# TheremineB.net
KiCad netlist of a schematic drawn in Altium Designer
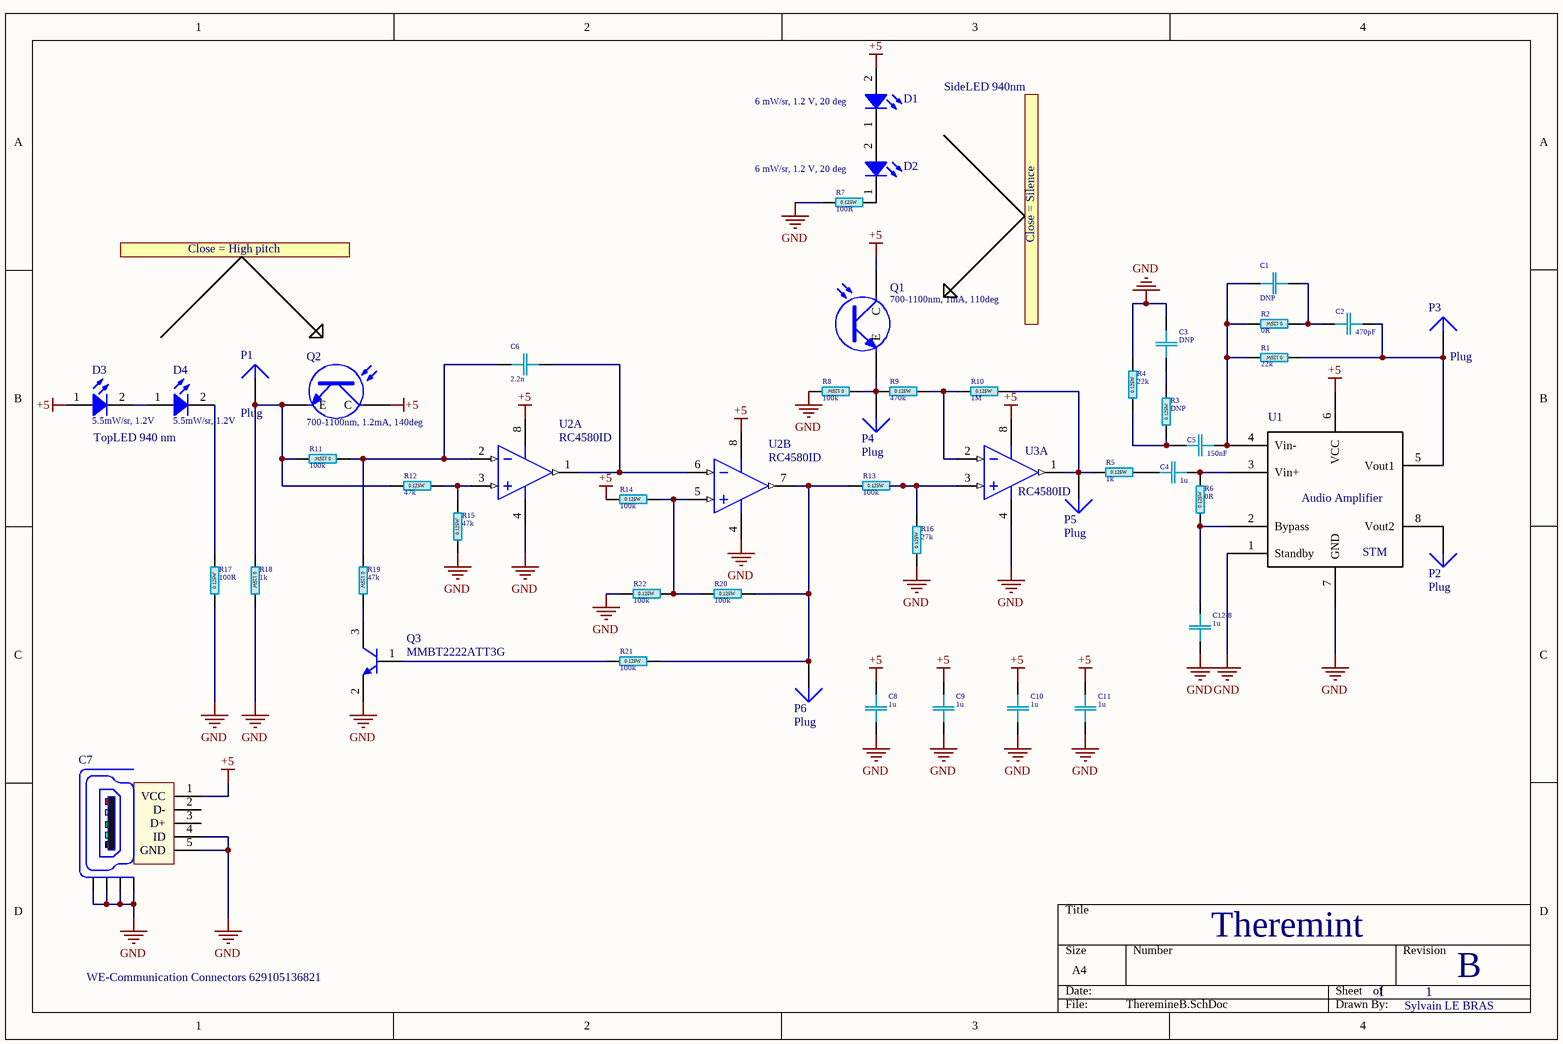
[diagram p0: TheremineB.SchDoc]

(export (version "E")
  (design (tool "Eeschema 10.0.6"))
  (components
    (comp (ref "C1")
      (value "DNP")
      (footprint "C 0805(2012)x1.25")
      (description "SMD 0805     16V X7R 10%")
      (fields
        (field (name "PART NUMBER") "CL21B105KBFNNNF")
        (field (name "MANUFACTURER") "Samsung")
        (field (name "PUBLISHER") "Hefest")
      )
      (libsource (lib "SMD Passive") (part "C 0805    16V X7R - 1u"))
    )
    (comp (ref "C2")
      (value "470pF")
      (footprint "C 0805(2012)x1.25")
      (description "SMD 0805     16V X7R 10%")
      (fields
        (field (name "PART NUMBER") "CL21B105KBFNNNF")
        (field (name "MANUFACTURER") "Samsung")
        (field (name "PUBLISHER") "Hefest")
      )
      (libsource (lib "SMD Passive") (part "C 0805    16V X7R - 1u"))
    )
    (comp (ref "C3")
      (value "DNP")
      (footprint "C 0805(2012)x1.25")
      (description "SMD 0805     16V X7R 10%")
      (fields
        (field (name "PART NUMBER") "CL21B105KBFNNNF")
        (field (name "MANUFACTURER") "Samsung")
        (field (name "PUBLISHER") "Hefest")
      )
      (libsource (lib "SMD Passive") (part "C 0805    16V X7R - 1u"))
    )
    (comp (ref "C4")
      (value "1u")
      (footprint "C 0805(2012)x1.25")
      (description "SMD 0805     16V X7R 10%")
      (fields
        (field (name "PART NUMBER") "CL21B105KBFNNNF")
        (field (name "MANUFACTURER") "Samsung")
        (field (name "PUBLISHER") "Hefest")
      )
      (libsource (lib "SMD Passive") (part "C 0805    16V X7R - 1u"))
    )
    (comp (ref "C5")
      (value "150nF")
      (footprint "C 0805(2012)x1.25")
      (description "SMD 0805     16V X7R 10%")
      (fields
        (field (name "PART NUMBER") "CL21B105KBFNNNF")
        (field (name "MANUFACTURER") "Samsung")
        (field (name "PUBLISHER") "Hefest")
      )
      (libsource (lib "SMD Passive") (part "C 0805    16V X7R - 1u"))
    )
    (comp (ref "C6")
      (value "2.2n")
      (footprint "C 0805(2012)x0.65")
      (description "SMD 0805     50V X7R 10%")
      (fields
        (field (name "PART NUMBER") "CL21B222KBNC")
        (field (name "MANUFACTURER") "Samsung")
        (field (name "PUBLISHER") "Hefest")
      )
      (libsource (lib "SMD Passive") (part "C 0805    50V X7R - 2.2n"))
    )
    (comp (ref "C7")
      (value "WE-Communication Connectors 629105136821")
      (footprint "629105136821")
      (description "WR-COM Micro USB SMT Type B")
      (fields
        (field (name "MANUFACTURER") "Würth Elektronik eiSos GmbH")
        (field (name "PARTNO") "629105136821")
        (field (name "CREATED BY") "Karrer Zheng")
      )
      (libsource (lib "WR-COM USB 2.0 Type B SMT Horizontal") (part "WE-Communication Connectors 629105136821"))
    )
    (comp (ref "C8")
      (value "1u")
      (footprint "C 0805(2012)x1.25")
      (description "SMD 0805     16V X7R 10%")
      (fields
        (field (name "PART NUMBER") "CL21B105KBFNNNF")
        (field (name "MANUFACTURER") "Samsung")
        (field (name "PUBLISHER") "Hefest")
      )
      (libsource (lib "SMD Passive") (part "C 0805    16V X7R - 1u"))
    )
    (comp (ref "C9")
      (value "1u")
      (footprint "C 0805(2012)x1.25")
      (description "SMD 0805     16V X7R 10%")
      (fields
        (field (name "PART NUMBER") "CL21B105KBFNNNF")
        (field (name "MANUFACTURER") "Samsung")
        (field (name "PUBLISHER") "Hefest")
      )
      (libsource (lib "SMD Passive") (part "C 0805    16V X7R - 1u"))
    )
    (comp (ref "C10")
      (value "1u")
      (footprint "C 0805(2012)x1.25")
      (description "SMD 0805     16V X7R 10%")
      (fields
        (field (name "PART NUMBER") "CL21B105KBFNNNF")
        (field (name "MANUFACTURER") "Samsung")
        (field (name "PUBLISHER") "Hefest")
      )
      (libsource (lib "SMD Passive") (part "C 0805    16V X7R - 1u"))
    )
    (comp (ref "C11")
      (value "1u")
      (footprint "C 0805(2012)x1.25")
      (description "SMD 0805     16V X7R 10%")
      (fields
        (field (name "PART NUMBER") "CL21B105KBFNNNF")
        (field (name "MANUFACTURER") "Samsung")
        (field (name "PUBLISHER") "Hefest")
      )
      (libsource (lib "SMD Passive") (part "C 0805    16V X7R - 1u"))
    )
    (comp (ref "C12-8")
      (value "1u")
      (footprint "C 0805(2012)x1.25")
      (description "SMD 0805     16V X7R 10%")
      (fields
        (field (name "PART NUMBER") "CL21B105KBFNNNF")
        (field (name "MANUFACTURER") "Samsung")
        (field (name "PUBLISHER") "Hefest")
      )
      (libsource (lib "SMD Passive") (part "C 0805    16V X7R - 1u"))
    )
    (comp (ref "D1")
      (value "6 mW/sr, 1.2 V, 20 deg")
      (footprint "WL-SISW_1206")
      (description "SMT Infrared Sideview LED Waterclear WL-SISW, size 1206, 6 mW/sr, 1.2 V, 20 deg")
      (fields (field (name "PART NUMBER") "15412094A2070") (field (name "PUBLISHER") "Wurth Elektronik"))
      (libsource (lib "WL-SISW SMT Infrared Sideview LED Waterclear") (part "15412094A2070"))
    )
    (comp (ref "D2")
      (value "6 mW/sr, 1.2 V, 20 deg")
      (footprint "WL-SISW_1206")
      (description "SMT Infrared Sideview LED Waterclear WL-SISW, size 1206, 6 mW/sr, 1.2 V, 20 deg")
      (fields (field (name "PART NUMBER") "15412094A2070") (field (name "PUBLISHER") "Wurth Elektronik"))
      (libsource (lib "WL-SISW SMT Infrared Sideview LED Waterclear") (part "15412094A2070"))
    )
    (comp (ref "D3")
      (value "5.5mW/sr, 1.2V")
      (footprint "WL-SICW_1206_H=1.21mm")
      (description "WL-SICW SMT Chip LED Infrared Waterclear, size 1206, 5.5mW/sr, 1.2V, 90deg")
      (fields (field (name "PART NUMBER") "15412094A9000") (field (name "PUBLISHER") "Wurth Elektronik"))
      (libsource (lib "WL-SICW SMT Chip LED Infrared Waterclear") (part "15412094A9000"))
    )
    (comp (ref "D4")
      (value "5.5mW/sr, 1.2V")
      (footprint "WL-SICW_1206_H=1.21mm")
      (description "WL-SICW SMT Chip LED Infrared Waterclear, size 1206, 5.5mW/sr, 1.2V, 90deg")
      (fields (field (name "PART NUMBER") "15412094A9000") (field (name "PUBLISHER") "Wurth Elektronik"))
      (libsource (lib "WL-SICW SMT Chip LED Infrared Waterclear") (part "15412094A9000"))
    )
    (comp (ref "P1")
      (value "Plug")
      (footprint "PIN1")
      (fields (field (name "PUBLISHER") "Altium Limited"))
      (libsource (lib "Miscellaneous Connectors") (part "Plug"))
    )
    (comp (ref "P2")
      (value "Plug")
      (footprint "PIN1")
      (fields (field (name "PUBLISHER") "Altium Limited"))
      (libsource (lib "Miscellaneous Connectors") (part "Plug"))
    )
    (comp (ref "P3")
      (value "Plug")
      (footprint "PIN1")
      (fields (field (name "PUBLISHER") "Altium Limited"))
      (libsource (lib "Miscellaneous Connectors") (part "Plug"))
    )
    (comp (ref "P4")
      (value "Plug")
      (footprint "PIN1")
      (fields (field (name "PUBLISHER") "Altium Limited"))
      (libsource (lib "Miscellaneous Connectors") (part "Plug"))
    )
    (comp (ref "P5")
      (value "Plug")
      (footprint "PIN1")
      (fields (field (name "PUBLISHER") "Altium Limited"))
      (libsource (lib "Miscellaneous Connectors") (part "Plug"))
    )
    (comp (ref "P6")
      (value "Plug")
      (footprint "PIN1")
      (fields (field (name "PUBLISHER") "Altium Limited"))
      (libsource (lib "Miscellaneous Connectors") (part "Plug"))
    )
    (comp (ref "Q1")
      (value "700-1100nm, 1mA, 110deg")
      (footprint "WL-STSB_1002")
      (description "WL-STSB SMT Phototransistor Chip Black, size 1002, 700-1100nm, 1mA, 110deg")
      (fields
        (field (name "MANUFACTURER PART NUMBER") "1541021NCA170")
        (field (name "PUBLISHER") "Wurth Elektronik")
      )
      (libsource (lib "WL-STSB SMT Phototransistor Chip Black") (part "1541021NCA170"))
    )
    (comp (ref "Q2")
      (value "700-1100nm, 1.2mA, 140deg")
      (footprint "WL-STCB_1206")
      (description "WL-STCB SMT Phototransistor Chip Black, size 1206, 700-1100nm, 1.2mA, 140deg")
      (fields
        (field (name "MANUFACTURER PART NUMBER") "1541201NEA400")
        (field (name "PUBLISHER") "Wurth Elektronik")
      )
      (libsource (lib "WL-STCB SMT Phototransistor Chip Black") (part "1541201NEA400"))
    )
    (comp (ref "Q3")
      (value "MMBT2222ATT3G")
      (footprint "ON SEMICONDUCTOR SC-75")
      (description "TRANS NPN 40V 0.6A SC75-3")
      (fields (field (name "MANUFACTURER") "ON Semiconductor"))
      (libsource (lib "Celestial Altium Library - altium_library") (part "ON SEMI NPN SC-75"))
    )
    (comp (ref "R1")
      (value "22k")
      (footprint "R 0805(2012)")
      (description "SMD 0805 0.125W 5% 150V")
      (fields
        (field (name "MANUFACTURER") "YAGEO")
        (field (name "POWER") "0.125W")
        (field (name "PUBLISHER") "Hefest")
      )
      (libsource (lib "") (part "R 0805-5%_3"))
    )
    (comp (ref "R2")
      (value "0R")
      (footprint "R 0805(2012)")
      (description "SMD 0805 0.125W 5% 150V")
      (fields
        (field (name "MANUFACTURER") "YAGEO")
        (field (name "POWER") "0.125W")
        (field (name "PUBLISHER") "Hefest")
      )
      (libsource (lib "") (part "R 0805-5%_3"))
    )
    (comp (ref "R3")
      (value "DNP")
      (footprint "R 0805(2012)")
      (description "SMD 0805 0.125W 5% 150V")
      (fields
        (field (name "MANUFACTURER") "YAGEO")
        (field (name "POWER") "0.125W")
        (field (name "PUBLISHER") "Hefest")
      )
      (libsource (lib "") (part "R 0805-5%_1"))
    )
    (comp (ref "R4")
      (value "22k")
      (footprint "R 0805(2012)")
      (description "SMD 0805 0.125W 5% 150V")
      (fields
        (field (name "MANUFACTURER") "YAGEO")
        (field (name "POWER") "0.125W")
        (field (name "PUBLISHER") "Hefest")
      )
      (libsource (lib "") (part "R 0805-5%_1"))
    )
    (comp (ref "R5")
      (value "1k")
      (footprint "R 0805(2012)")
      (description "SMD 0805 0.125W 5% 150V")
      (fields
        (field (name "MANUFACTURER") "YAGEO")
        (field (name "POWER") "0.125W")
        (field (name "PUBLISHER") "Hefest")
      )
      (libsource (lib "SMD Passive") (part "R 0805-5%"))
    )
    (comp (ref "R6")
      (value "0R")
      (footprint "R 0805(2012)")
      (description "SMD 0805 0.125W 5% 150V")
      (fields
        (field (name "MANUFACTURER") "YAGEO")
        (field (name "POWER") "0.125W")
        (field (name "PUBLISHER") "Hefest")
      )
      (libsource (lib "") (part "R 0805-5%_1"))
    )
    (comp (ref "R7")
      (value "100R")
      (footprint "R 0805(2012)")
      (description "SMD 0805 0.125W 5% 150V")
      (fields
        (field (name "MANUFACTURER") "YAGEO")
        (field (name "POWER") "0.125W")
        (field (name "PUBLISHER") "Hefest")
      )
      (libsource (lib "SMD Passive") (part "R 0805-5%"))
    )
    (comp (ref "R8")
      (value "100k")
      (footprint "R 0805(2012)")
      (description "SMD 0805 0.125W 5% 150V")
      (fields
        (field (name "MANUFACTURER") "YAGEO")
        (field (name "POWER") "0.125W")
        (field (name "PUBLISHER") "Hefest")
      )
      (libsource (lib "") (part "R 0805-5%_3"))
    )
    (comp (ref "R9")
      (value "470k")
      (footprint "R 0805(2012)")
      (description "SMD 0805 0.125W 5% 150V")
      (fields
        (field (name "MANUFACTURER") "YAGEO")
        (field (name "POWER") "0.125W")
        (field (name "PUBLISHER") "Hefest")
      )
      (libsource (lib "SMD Passive") (part "R 0805-5%"))
    )
    (comp (ref "R10")
      (value "1M")
      (footprint "R 0805(2012)")
      (description "SMD 0805 0.125W 5% 150V")
      (fields
        (field (name "MANUFACTURER") "YAGEO")
        (field (name "POWER") "0.125W")
        (field (name "PUBLISHER") "Hefest")
      )
      (libsource (lib "SMD Passive") (part "R 0805-5%"))
    )
    (comp (ref "R11")
      (value "100k")
      (footprint "R 0805(2012)")
      (description "SMD 0805 0.125W 5% 150V")
      (fields
        (field (name "MANUFACTURER") "YAGEO")
        (field (name "POWER") "0.125W")
        (field (name "PUBLISHER") "Hefest")
      )
      (libsource (lib "") (part "R 0805-5%_3"))
    )
    (comp (ref "R12")
      (value "47k")
      (footprint "R 0805(2012)")
      (description "SMD 0805 0.125W 5% 150V")
      (fields
        (field (name "MANUFACTURER") "YAGEO")
        (field (name "POWER") "0.125W")
        (field (name "PUBLISHER") "Hefest")
      )
      (libsource (lib "SMD Passive") (part "R 0805-5%"))
    )
    (comp (ref "R13")
      (value "100k")
      (footprint "R 0805(2012)")
      (description "SMD 0805 0.125W 5% 150V")
      (fields
        (field (name "MANUFACTURER") "YAGEO")
        (field (name "POWER") "0.125W")
        (field (name "PUBLISHER") "Hefest")
      )
      (libsource (lib "SMD Passive") (part "R 0805-5%"))
    )
    (comp (ref "R14")
      (value "100k")
      (footprint "R 0805(2012)")
      (description "SMD 0805 0.125W 5% 150V")
      (fields
        (field (name "MANUFACTURER") "YAGEO")
        (field (name "POWER") "0.125W")
        (field (name "PUBLISHER") "Hefest")
      )
      (libsource (lib "SMD Passive") (part "R 0805-5%"))
    )
    (comp (ref "R15")
      (value "47k")
      (footprint "R 0805(2012)")
      (description "SMD 0805 0.125W 5% 150V")
      (fields
        (field (name "MANUFACTURER") "YAGEO")
        (field (name "POWER") "0.125W")
        (field (name "PUBLISHER") "Hefest")
      )
      (libsource (lib "") (part "R 0805-5%_1"))
    )
    (comp (ref "R16")
      (value "27k")
      (footprint "R 0805(2012)")
      (description "SMD 0805 0.125W 5% 150V")
      (fields
        (field (name "MANUFACTURER") "YAGEO")
        (field (name "POWER") "0.125W")
        (field (name "PUBLISHER") "Hefest")
      )
      (libsource (lib "") (part "R 0805-5%_1"))
    )
    (comp (ref "R17")
      (value "100R")
      (footprint "R 0805(2012)")
      (description "SMD 0805 0.125W 5% 150V")
      (fields
        (field (name "MANUFACTURER") "YAGEO")
        (field (name "POWER") "0.125W")
        (field (name "PUBLISHER") "Hefest")
      )
      (libsource (lib "") (part "R 0805-5%_1"))
    )
    (comp (ref "R18")
      (value "1k")
      (footprint "R 0805(2012)")
      (description "SMD 0805 0.125W 5% 150V")
      (fields
        (field (name "MANUFACTURER") "YAGEO")
        (field (name "POWER") "0.125W")
        (field (name "PUBLISHER") "Hefest")
      )
      (libsource (lib "") (part "R 0805-5%_2"))
    )
    (comp (ref "R19")
      (value "47k")
      (footprint "R 0805(2012)")
      (description "SMD 0805 0.125W 5% 150V")
      (fields
        (field (name "MANUFACTURER") "YAGEO")
        (field (name "POWER") "0.125W")
        (field (name "PUBLISHER") "Hefest")
      )
      (libsource (lib "") (part "R 0805-5%_2"))
    )
    (comp (ref "R20")
      (value "100k")
      (footprint "R 0805(2012)")
      (description "SMD 0805 0.125W 5% 150V")
      (fields
        (field (name "MANUFACTURER") "YAGEO")
        (field (name "POWER") "0.125W")
        (field (name "PUBLISHER") "Hefest")
      )
      (libsource (lib "SMD Passive") (part "R 0805-5%"))
    )
    (comp (ref "R21")
      (value "100k")
      (footprint "R 0805(2012)")
      (description "SMD 0805 0.125W 5% 150V")
      (fields
        (field (name "MANUFACTURER") "YAGEO")
        (field (name "POWER") "0.125W")
        (field (name "PUBLISHER") "Hefest")
      )
      (libsource (lib "SMD Passive") (part "R 0805-5%"))
    )
    (comp (ref "R22")
      (value "100k")
      (footprint "R 0805(2012)")
      (description "SMD 0805 0.125W 5% 150V")
      (fields
        (field (name "MANUFACTURER") "YAGEO")
        (field (name "POWER") "0.125W")
        (field (name "PUBLISHER") "Hefest")
      )
      (libsource (lib "SMD Passive") (part "R 0805-5%"))
    )
    (comp (ref "U1")
      (value "STM")
      (footprint "SO8_M")
      (description "Audio Amplifier")
      (libsource (lib "TS4871") (part "TS4871"))
    )
    (comp (ref "U2")
      (value "RC4580ID")
      (footprint "TI-D8_N")
      (fields (field (name "MANUFACTURER") "Texas Instruments"))
      (libsource (lib "TI Amplifiers and Linear Operational Amplifier General Purpose") (part "RC4580ID"))
    )
    (comp (ref "U3")
      (value "RC4580ID")
      (footprint "TI-D8_N")
      (fields (field (name "MANUFACTURER") "Texas Instruments"))
      (libsource (lib "TI Amplifiers and Linear Operational Amplifier General Purpose") (part "RC4580ID"))
    )
  )
  (nets
    (net (code "1") (name "+5") (class "Default")
      (node (ref "C10") (pin "2") (pinfunction "2_2") (pintype "passive"))
      (node (ref "C11") (pin "2") (pinfunction "2_2") (pintype "passive"))
      (node (ref "C7") (pin "1") (pinfunction "VCC_1") (pintype "passive"))
      (node (ref "C8") (pin "2") (pinfunction "2_2") (pintype "passive"))
      (node (ref "C9") (pin "2") (pinfunction "2_2") (pintype "passive"))
      (node (ref "D1") (pin "2") (pinfunction "A_2") (pintype "passive"))
      (node (ref "D3") (pin "1") (pinfunction "A_1") (pintype "passive"))
      (node (ref "Q1") (pin "1") (pinfunction "C_1") (pintype "passive"))
      (node (ref "Q2") (pin "1") (pinfunction "C_1") (pintype "passive"))
      (node (ref "R14") (pin "1") (pinfunction "1_1") (pintype "passive"))
      (node (ref "U1") (pin "6") (pinfunction "VCC_6") (pintype "passive"))
      (node (ref "U2") (pin "8") (pinfunction "VCC+_8") (pintype "power_in"))
      (node (ref "U3") (pin "8") (pinfunction "VCC+_8") (pintype "power_in"))
    )
    (net (code "2") (name "GND") (class "Default")
      (node (ref "C10") (pin "1") (pinfunction "1_1") (pintype "passive"))
      (node (ref "C11") (pin "1") (pinfunction "1_1") (pintype "passive"))
      (node (ref "C12-8") (pin "2") (pinfunction "2_2") (pintype "passive"))
      (node (ref "C3") (pin "2") (pinfunction "2_2") (pintype "passive"))
      (node (ref "C7") (pin "4") (pinfunction "ID_4") (pintype "passive"))
      (node (ref "C7") (pin "5") (pinfunction "GND_5") (pintype "passive"))
      (node (ref "C7") (pin "Z1") (pinfunction "Shield_Z1") (pintype "passive"))
      (node (ref "C7") (pin "Z2") (pinfunction "Shield_Z2") (pintype "passive"))
      (node (ref "C7") (pin "Z3") (pinfunction "Shield_Z3") (pintype "passive"))
      (node (ref "C7") (pin "Z4") (pinfunction "Shield_Z4") (pintype "passive"))
      (node (ref "C8") (pin "1") (pinfunction "1_1") (pintype "passive"))
      (node (ref "C9") (pin "1") (pinfunction "1_1") (pintype "passive"))
      (node (ref "Q3") (pin "2") (pinfunction "E_2") (pintype "passive"))
      (node (ref "R15") (pin "1") (pinfunction "1_1") (pintype "passive"))
      (node (ref "R16") (pin "1") (pinfunction "1_1") (pintype "passive"))
      (node (ref "R17") (pin "1") (pinfunction "1_1") (pintype "passive"))
      (node (ref "R18") (pin "2") (pinfunction "2_2") (pintype "passive"))
      (node (ref "R22") (pin "1") (pinfunction "1_1") (pintype "passive"))
      (node (ref "R4") (pin "2") (pinfunction "2_2") (pintype "passive"))
      (node (ref "R7") (pin "1") (pinfunction "1_1") (pintype "passive"))
      (node (ref "R8") (pin "2") (pinfunction "2_2") (pintype "passive"))
      (node (ref "U1") (pin "1") (pinfunction "Standby_1") (pintype "passive"))
      (node (ref "U1") (pin "7") (pinfunction "GND_7") (pintype "passive"))
      (node (ref "U2") (pin "4") (pinfunction "VCC-_4") (pintype "power_in"))
      (node (ref "U3") (pin "4") (pinfunction "VCC-_4") (pintype "power_in"))
    )
    (net (code "3") (name "Net-(C1-Pad2)") (class "Default")
      (node (ref "C1") (pin "2") (pinfunction "2_2") (pintype "passive"))
      (node (ref "C2") (pin "1") (pinfunction "1_1") (pintype "passive"))
      (node (ref "R2") (pin "1") (pinfunction "1_1") (pintype "passive"))
    )
    (net (code "4") (name "Net-(C3-Pad1)") (class "Default")
      (node (ref "C3") (pin "1") (pinfunction "1_1") (pintype "passive"))
      (node (ref "R3") (pin "2") (pinfunction "2_2") (pintype "passive"))
    )
    (net (code "5") (name "Net-(C4-Pad1)") (class "Default")
      (node (ref "C4") (pin "1") (pinfunction "1_1") (pintype "passive"))
      (node (ref "R5") (pin "2") (pinfunction "2_2") (pintype "passive"))
    )
    (net (code "6") (name "Net-(C5-Pad1)") (class "Default")
      (node (ref "C5") (pin "1") (pinfunction "1_1") (pintype "passive"))
      (node (ref "R3") (pin "1") (pinfunction "1_1") (pintype "passive"))
      (node (ref "R4") (pin "1") (pinfunction "1_1") (pintype "passive"))
    )
    (net (code "7") (name "Net-(D1-K)") (class "Default")
      (node (ref "D1") (pin "1") (pinfunction "K_1") (pintype "passive"))
      (node (ref "D2") (pin "2") (pinfunction "A_2") (pintype "passive"))
    )
    (net (code "8") (name "Net-(D2-K)") (class "Default")
      (node (ref "D2") (pin "1") (pinfunction "K_1") (pintype "passive"))
      (node (ref "R7") (pin "2") (pinfunction "2_2") (pintype "passive"))
    )
    (net (code "9") (name "Net-(D3-K)") (class "Default")
      (node (ref "D3") (pin "2") (pinfunction "K_2") (pintype "passive"))
      (node (ref "D4") (pin "1") (pinfunction "A_1") (pintype "passive"))
    )
    (net (code "10") (name "Net-(D4-K)") (class "Default")
      (node (ref "D4") (pin "2") (pinfunction "K_2") (pintype "passive"))
      (node (ref "R17") (pin "2") (pinfunction "2_2") (pintype "passive"))
    )
    (net (code "11") (name "Net-(Q1-E)") (class "Default")
      (node (ref "P4") (pin "1") (pinfunction "1_1") (pintype "passive"))
      (node (ref "Q1") (pin "2") (pinfunction "E_2") (pintype "passive"))
      (node (ref "R8") (pin "1") (pinfunction "1_1") (pintype "passive"))
      (node (ref "R9") (pin "1") (pinfunction "1_1") (pintype "passive"))
    )
    (net (code "12") (name "Net-(Q2-E)") (class "Default")
      (node (ref "P1") (pin "1") (pinfunction "1_1") (pintype "passive"))
      (node (ref "Q2") (pin "2") (pinfunction "E_2") (pintype "passive"))
      (node (ref "R11") (pin "2") (pinfunction "2_2") (pintype "passive"))
      (node (ref "R12") (pin "1") (pinfunction "1_1") (pintype "passive"))
      (node (ref "R18") (pin "1") (pinfunction "1_1") (pintype "passive"))
    )
    (net (code "13") (name "Net-(Q3-B)") (class "Default")
      (node (ref "Q3") (pin "1") (pinfunction "B_1") (pintype "passive"))
      (node (ref "R21") (pin "1") (pinfunction "1_1") (pintype "passive"))
    )
    (net (code "14") (name "Net-(Q3-C)") (class "Default")
      (node (ref "Q3") (pin "3") (pinfunction "C_3") (pintype "passive"))
      (node (ref "R19") (pin "2") (pinfunction "2_2") (pintype "passive"))
    )
    (net (code "15") (name "Net-(U1-Bypass)") (class "Default")
      (node (ref "C12-8") (pin "1") (pinfunction "1_1") (pintype "passive"))
      (node (ref "R6") (pin "1") (pinfunction "1_1") (pintype "passive"))
      (node (ref "U1") (pin "2") (pinfunction "Bypass_2") (pintype "passive"))
    )
    (net (code "16") (name "Net-(U1-Vin+)") (class "Default")
      (node (ref "C4") (pin "2") (pinfunction "2_2") (pintype "passive"))
      (node (ref "R6") (pin "2") (pinfunction "2_2") (pintype "passive"))
      (node (ref "U1") (pin "3") (pinfunction "Vin+_3") (pintype "passive"))
    )
    (net (code "17") (name "Net-(U1-Vin-)") (class "Default")
      (node (ref "C1") (pin "1") (pinfunction "1_1") (pintype "passive"))
      (node (ref "C5") (pin "2") (pinfunction "2_2") (pintype "passive"))
      (node (ref "R1") (pin "2") (pinfunction "2_2") (pintype "passive"))
      (node (ref "R2") (pin "2") (pinfunction "2_2") (pintype "passive"))
      (node (ref "U1") (pin "4") (pinfunction "Vin-_4") (pintype "passive"))
    )
    (net (code "18") (name "Net-(U1-Vout1)") (class "Default")
      (node (ref "C2") (pin "2") (pinfunction "2_2") (pintype "passive"))
      (node (ref "P3") (pin "1") (pinfunction "1_1") (pintype "passive"))
      (node (ref "R1") (pin "1") (pinfunction "1_1") (pintype "passive"))
      (node (ref "U1") (pin "5") (pinfunction "Vout1_5") (pintype "passive"))
    )
    (net (code "19") (name "Net-(U1-Vout2)") (class "Default")
      (node (ref "P2") (pin "1") (pinfunction "1_1") (pintype "passive"))
      (node (ref "U1") (pin "8") (pinfunction "Vout2_8") (pintype "passive"))
    )
    (net (code "20") (name "Net-(U2A-IN1+)") (class "Default")
      (node (ref "R12") (pin "2") (pinfunction "2_2") (pintype "passive"))
      (node (ref "R15") (pin "2") (pinfunction "2_2") (pintype "passive"))
      (node (ref "U2") (pin "3") (pinfunction "IN1+_3") (pintype "input"))
    )
    (net (code "21") (name "Net-(U2A-IN1-)") (class "Default")
      (node (ref "C6") (pin "1") (pinfunction "1_1") (pintype "passive"))
      (node (ref "R11") (pin "1") (pinfunction "1_1") (pintype "passive"))
      (node (ref "R19") (pin "1") (pinfunction "1_1") (pintype "passive"))
      (node (ref "U2") (pin "2") (pinfunction "IN1-_2") (pintype "input"))
    )
    (net (code "22") (name "Net-(U2A-OUT1)") (class "Default")
      (node (ref "C6") (pin "2") (pinfunction "2_2") (pintype "passive"))
      (node (ref "U2") (pin "1") (pinfunction "OUT1_1") (pintype "output"))
      (node (ref "U2") (pin "6") (pinfunction "IN2-_6") (pintype "input"))
    )
    (net (code "23") (name "Net-(U2B-IN2+)") (class "Default")
      (node (ref "R14") (pin "2") (pinfunction "2_2") (pintype "passive"))
      (node (ref "R20") (pin "1") (pinfunction "1_1") (pintype "passive"))
      (node (ref "R22") (pin "2") (pinfunction "2_2") (pintype "passive"))
      (node (ref "U2") (pin "5") (pinfunction "IN2+_5") (pintype "input"))
    )
    (net (code "24") (name "Net-(U2B-OUT2)") (class "Default")
      (node (ref "P6") (pin "1") (pinfunction "1_1") (pintype "passive"))
      (node (ref "R13") (pin "1") (pinfunction "1_1") (pintype "passive"))
      (node (ref "R20") (pin "2") (pinfunction "2_2") (pintype "passive"))
      (node (ref "R21") (pin "2") (pinfunction "2_2") (pintype "passive"))
      (node (ref "U2") (pin "7") (pinfunction "OUT2_7") (pintype "output"))
    )
    (net (code "25") (name "Net-(U3A-IN1+)") (class "Default")
      (node (ref "R13") (pin "2") (pinfunction "2_2") (pintype "passive"))
      (node (ref "R16") (pin "2") (pinfunction "2_2") (pintype "passive"))
      (node (ref "U3") (pin "3") (pinfunction "IN1+_3") (pintype "input"))
    )
    (net (code "26") (name "Net-(U3A-IN1-)") (class "Default")
      (node (ref "R10") (pin "1") (pinfunction "1_1") (pintype "passive"))
      (node (ref "R9") (pin "2") (pinfunction "2_2") (pintype "passive"))
      (node (ref "U3") (pin "2") (pinfunction "IN1-_2") (pintype "input"))
    )
    (net (code "27") (name "Net-(U3A-OUT1)") (class "Default")
      (node (ref "P5") (pin "1") (pinfunction "1_1") (pintype "passive"))
      (node (ref "R10") (pin "2") (pinfunction "2_2") (pintype "passive"))
      (node (ref "R5") (pin "1") (pinfunction "1_1") (pintype "passive"))
      (node (ref "U3") (pin "1") (pinfunction "OUT1_1") (pintype "output"))
    )
    (net (code "28") (name "unconnected-(C7-D+-Pad3)") (class "Default")
      (node (ref "C7") (pin "3") (pinfunction "D+_3") (pintype "passive"))
    )
    (net (code "29") (name "unconnected-(C7-D--Pad2)") (class "Default")
      (node (ref "C7") (pin "2") (pinfunction "D-_2") (pintype "passive"))
    )
  )
)
